# USB_Power.net
KiCad netlist of a schematic drawn in Altium Designer
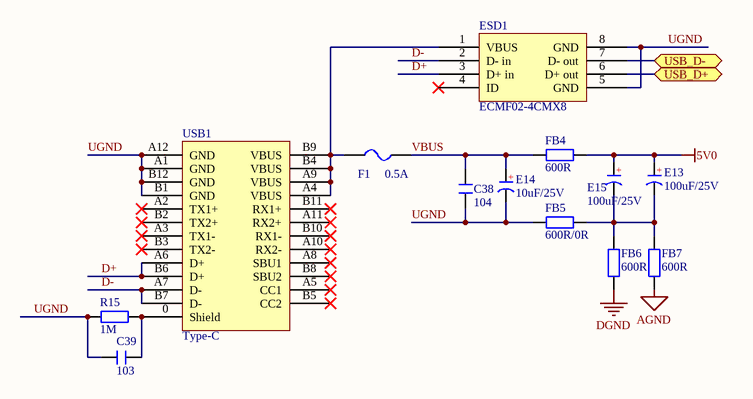
[diagram p0: USB_Power.SchDoc]

(export (version "E")
  (design (tool "Eeschema 10.0.6"))
  (components
    (comp (ref "C38")
      (value "104")
      (footprint "C 0603_L")
      (description "贴片电容")
      (libsource (lib "0.1 - 电阻-电容-电感") (part "C"))
    )
    (comp (ref "C39")
      (value "103")
      (footprint "C 0603_L")
      (description "贴片电容")
      (libsource (lib "0.1 - 电阻-电容-电感") (part "C"))
    )
    (comp (ref "E13")
      (value "100uF/25V")
      (footprint "CD D(7343)")
      (description "贴片钽电容")
      (libsource (lib "0.1 - 电阻-电容-电感") (part "CT"))
    )
    (comp (ref "E14")
      (value "10uF/25V")
      (footprint "CD A(3216)")
      (description "贴片钽电容")
      (libsource (lib "0.1 - 电阻-电容-电感") (part "CT"))
    )
    (comp (ref "E15")
      (value "100uF/25V")
      (footprint "CD D(7343)")
      (description "贴片钽电容")
      (libsource (lib "0.1 - 电阻-电容-电感") (part "CT"))
    )
    (comp (ref "ESD1")
      (value "ECMF02-4CMX8")
      (footprint "QFN8L")
      (description "Common mode filter with ESD protection for USB 2.0 interface")
      (libsource (lib "防护器件") (part "ECMF02-4CMX8"))
    )
    (comp (ref "F1")
      (value "0.5A")
      (footprint "FU 1206")
      (description "贴片保险丝")
      (fields (field (name "版权归属") "封装库来自淘宝卖家 ID：黄晶宝石"))
      (libsource (lib "0.5 - 保险丝-晶振-光耦") (part "FU"))
    )
    (comp (ref "FB4")
      (value "600R")
      (footprint "R 0805_L")
      (description "贴片电阻")
      (libsource (lib "0.1 - 电阻-电容-电感") (part "R"))
    )
    (comp (ref "FB5")
      (value "600R/0R")
      (footprint "R 0805_L")
      (description "贴片电阻")
      (libsource (lib "0.1 - 电阻-电容-电感") (part "R"))
    )
    (comp (ref "FB6")
      (value "600R")
      (footprint "R 0805_L")
      (description "贴片电阻")
      (libsource (lib "0.1 - 电阻-电容-电感") (part "R"))
    )
    (comp (ref "FB7")
      (value "600R")
      (footprint "R 0805_L")
      (description "贴片电阻")
      (libsource (lib "0.1 - 电阻-电容-电感") (part "R"))
    )
    (comp (ref "R15")
      (value "1M")
      (footprint "R 0603_L")
      (description "贴片电阻")
      (libsource (lib "0.1 - 电阻-电容-电感") (part "R"))
    )
    (comp (ref "USB1")
      (value "Type-C")
      (footprint "USB-TYPE-C_16PIN-MALE-TYPE-C-31-M-12")
      (libsource (lib "type-c") (part "Type-C"))
    )
  )
  (nets
    (net (code "1") (name "/D+") (class "Default")
      (node (ref "ESD1") (pin "3") (pinfunction "D+_in_3") (pintype "passive"))
      (node (ref "USB1") (pin "A6") (pinfunction "D+_A6") (pintype "passive"))
      (node (ref "USB1") (pin "B6") (pinfunction "D+_B6") (pintype "passive"))
    )
    (net (code "2") (name "/D-") (class "Default")
      (node (ref "ESD1") (pin "2") (pinfunction "D-_in_2") (pintype "passive"))
      (node (ref "USB1") (pin "A7") (pinfunction "D-_A7") (pintype "passive"))
      (node (ref "USB1") (pin "B7") (pinfunction "D-_B7") (pintype "passive"))
    )
    (net (code "3") (name "/UGND") (class "Default")
      (node (ref "C38") (pin "1") (pinfunction "1_1") (pintype "passive"))
      (node (ref "C39") (pin "2") (pinfunction "2_2") (pintype "passive"))
      (node (ref "E14") (pin "2") (pinfunction "K_2") (pintype "passive"))
      (node (ref "ESD1") (pin "5") (pinfunction "GND_5") (pintype "passive"))
      (node (ref "ESD1") (pin "8") (pinfunction "GND_8") (pintype "passive"))
      (node (ref "FB5") (pin "1") (pinfunction "1_1") (pintype "passive"))
      (node (ref "R15") (pin "2") (pinfunction "2_2") (pintype "passive"))
      (node (ref "USB1") (pin "A1") (pinfunction "GND_A1") (pintype "passive"))
      (node (ref "USB1") (pin "A12") (pinfunction "GND_A12") (pintype "passive"))
      (node (ref "USB1") (pin "B1") (pinfunction "GND_B1") (pintype "passive"))
      (node (ref "USB1") (pin "B12") (pinfunction "GND_B12") (pintype "passive"))
    )
    (net (code "4") (name "/USB_D+") (class "Default")
      (node (ref "ESD1") (pin "6") (pinfunction "D+_out_6") (pintype "passive"))
    )
    (net (code "5") (name "/USB_D-") (class "Default")
      (node (ref "ESD1") (pin "7") (pinfunction "D-_out_7") (pintype "passive"))
    )
    (net (code "6") (name "/VBUS") (class "Default")
      (node (ref "C38") (pin "2") (pinfunction "2_2") (pintype "passive"))
      (node (ref "E14") (pin "1") (pinfunction "A_1") (pintype "passive"))
      (node (ref "F1") (pin "2") (pinfunction "2_2") (pintype "passive"))
      (node (ref "FB4") (pin "1") (pinfunction "1_1") (pintype "passive"))
    )
    (net (code "7") (name "5V0") (class "Default")
      (node (ref "E13") (pin "1") (pinfunction "A_1") (pintype "passive"))
      (node (ref "E15") (pin "1") (pinfunction "A_1") (pintype "passive"))
      (node (ref "FB4") (pin "2") (pinfunction "2_2") (pintype "passive"))
    )
    (net (code "8") (name "AGND") (class "Default")
      (node (ref "FB7") (pin "1") (pinfunction "1_1") (pintype "passive"))
    )
    (net (code "9") (name "DGND") (class "Default")
      (node (ref "FB6") (pin "1") (pinfunction "1_1") (pintype "passive"))
    )
    (net (code "10") (name "Net-(E13-K)") (class "Default")
      (node (ref "E13") (pin "2") (pinfunction "K_2") (pintype "passive"))
      (node (ref "E15") (pin "2") (pinfunction "K_2") (pintype "passive"))
      (node (ref "FB5") (pin "2") (pinfunction "2_2") (pintype "passive"))
      (node (ref "FB6") (pin "2") (pinfunction "2_2") (pintype "passive"))
      (node (ref "FB7") (pin "2") (pinfunction "2_2") (pintype "passive"))
    )
    (net (code "11") (name "Net-(ESD1-VBUS)") (class "Default")
      (node (ref "ESD1") (pin "1") (pinfunction "VBUS_1") (pintype "passive"))
      (node (ref "F1") (pin "1") (pinfunction "1_1") (pintype "passive"))
      (node (ref "USB1") (pin "A4") (pinfunction "VBUS_A4") (pintype "passive"))
      (node (ref "USB1") (pin "A9") (pinfunction "VBUS_A9") (pintype "passive"))
      (node (ref "USB1") (pin "B4") (pinfunction "VBUS_B4") (pintype "passive"))
      (node (ref "USB1") (pin "B9") (pinfunction "VBUS_B9") (pintype "passive"))
    )
    (net (code "12") (name "Net-(USB1-Shield)") (class "Default")
      (node (ref "C39") (pin "1") (pinfunction "1_1") (pintype "passive"))
      (node (ref "R15") (pin "1") (pinfunction "1_1") (pintype "passive"))
      (node (ref "USB1") (pin "0") (pinfunction "Shield_0") (pintype "passive"))
    )
    (net (code "13") (name "unconnected-(ESD1-ID-Pad4)") (class "Default")
      (node (ref "ESD1") (pin "4") (pinfunction "ID_4") (pintype "passive+no_connect"))
    )
    (net (code "14") (name "unconnected-(USB1-CC1-PadA5)") (class "Default")
      (node (ref "USB1") (pin "A5") (pinfunction "CC1_A5") (pintype "passive+no_connect"))
    )
    (net (code "15") (name "unconnected-(USB1-CC2-PadB5)") (class "Default")
      (node (ref "USB1") (pin "B5") (pinfunction "CC2_B5") (pintype "passive+no_connect"))
    )
    (net (code "16") (name "unconnected-(USB1-RX1+-PadB11)") (class "Default")
      (node (ref "USB1") (pin "B11") (pinfunction "RX1+_B11") (pintype "passive+no_connect"))
    )
    (net (code "17") (name "unconnected-(USB1-RX1--PadB10)") (class "Default")
      (node (ref "USB1") (pin "B10") (pinfunction "RX1-_B10") (pintype "passive+no_connect"))
    )
    (net (code "18") (name "unconnected-(USB1-RX2+-PadA11)") (class "Default")
      (node (ref "USB1") (pin "A11") (pinfunction "RX2+_A11") (pintype "passive+no_connect"))
    )
    (net (code "19") (name "unconnected-(USB1-RX2--PadA10)") (class "Default")
      (node (ref "USB1") (pin "A10") (pinfunction "RX2-_A10") (pintype "passive+no_connect"))
    )
    (net (code "20") (name "unconnected-(USB1-SBU1-PadA8)") (class "Default")
      (node (ref "USB1") (pin "A8") (pinfunction "SBU1_A8") (pintype "passive+no_connect"))
    )
    (net (code "21") (name "unconnected-(USB1-SBU2-PadB8)") (class "Default")
      (node (ref "USB1") (pin "B8") (pinfunction "SBU2_B8") (pintype "passive+no_connect"))
    )
    (net (code "22") (name "unconnected-(USB1-TX1+-PadA2)") (class "Default")
      (node (ref "USB1") (pin "A2") (pinfunction "TX1+_A2") (pintype "passive+no_connect"))
    )
    (net (code "23") (name "unconnected-(USB1-TX1--PadA3)") (class "Default")
      (node (ref "USB1") (pin "A3") (pinfunction "TX1-_A3") (pintype "passive+no_connect"))
    )
    (net (code "24") (name "unconnected-(USB1-TX2+-PadB2)") (class "Default")
      (node (ref "USB1") (pin "B2") (pinfunction "TX2+_B2") (pintype "passive+no_connect"))
    )
    (net (code "25") (name "unconnected-(USB1-TX2--PadB3)") (class "Default")
      (node (ref "USB1") (pin "B3") (pinfunction "TX2-_B3") (pintype "passive+no_connect"))
    )
  )
)
